# BidirectionalBusCape.net
KiCad netlist of a schematic drawn in EAGLE
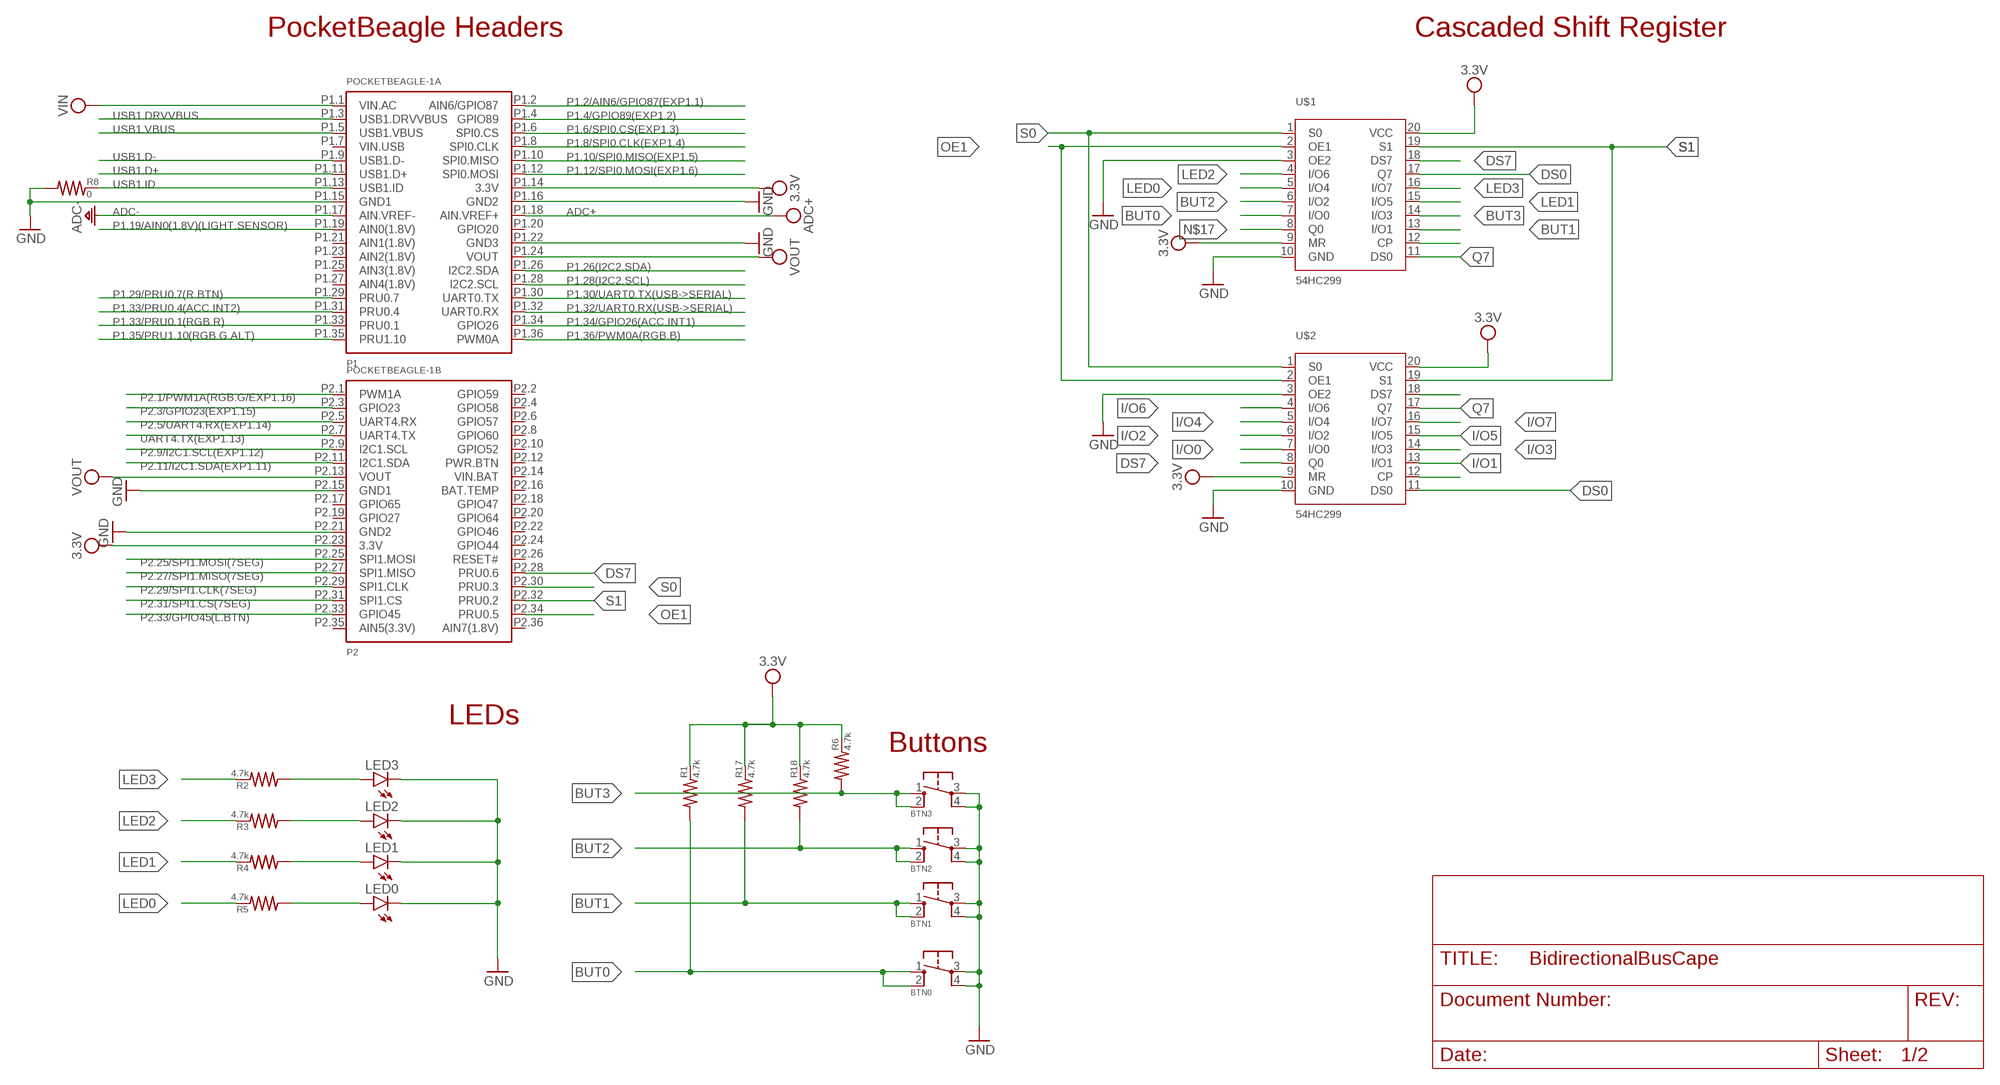
[diagram p0: schematic, sheet 1]

(export (version "E")
  (design (tool "Eeschema 10.0.6"))
  (components
    (comp (ref "BTN0")
      (value "TACTILE.SWITCH-6MM")
      (footprint "eagle-import:6MM_TACTILE-SWITCH")
      (libsource (lib "eagle-import") (part "TACTILE.SWITCH-6MM"))
    )
    (comp (ref "BTN1")
      (value "TACTILE.SWITCH-6MM")
      (footprint "eagle-import:6MM_TACTILE-SWITCH")
      (libsource (lib "eagle-import") (part "TACTILE.SWITCH-6MM"))
    )
    (comp (ref "BTN2")
      (value "TACTILE.SWITCH-6MM")
      (footprint "eagle-import:6MM_TACTILE-SWITCH")
      (libsource (lib "eagle-import") (part "TACTILE.SWITCH-6MM"))
    )
    (comp (ref "BTN3")
      (value "TACTILE.SWITCH-3X3.5MM")
      (footprint "eagle-import:3X3.5MM-TACTILE-SWITCH")
      (libsource (lib "eagle-import") (part "TACTILE.SWITCH-3X3.5MM"))
    )
    (comp (ref "LED0")
      (value "LEDCHIPLED_0603")
      (footprint "eagle-import:CHIPLED_0603")
      (libsource (lib "eagle-import") (part "LEDCHIPLED_0603"))
    )
    (comp (ref "LED1")
      (value "LEDCHIPLED_0603")
      (footprint "eagle-import:CHIPLED_0603")
      (libsource (lib "eagle-import") (part "LEDCHIPLED_0603"))
    )
    (comp (ref "LED2")
      (value "LEDCHIPLED_0603")
      (footprint "eagle-import:CHIPLED_0603")
      (libsource (lib "eagle-import") (part "LEDCHIPLED_0603"))
    )
    (comp (ref "LED3")
      (value "LEDCHIPLED_0603")
      (footprint "eagle-import:CHIPLED_0603")
      (libsource (lib "eagle-import") (part "LEDCHIPLED_0603"))
    )
    (comp (ref "POCKETBEAGLE-1")
      (value "POCKETBEAGLE-(ORIGIN-CENTER)-SMT.PADS(ONLY)-NO.RESTRICT")
      (footprint "eagle-import:POCKETBEAGLE-(ORIGIN-CENTER)-SMT.PADS(ONLY)-NO.RESTRICT")
      (libsource (lib "eagle-import") (part "POCKETBEAGLE-(ORIGIN-CENTER)-SMT.PADS(ONLY)-NO.RESTRICT"))
    )
    (comp (ref "R1")
      (value "4.7k")
      (footprint "eagle-import:0402")
      (libsource (lib "eagle-import") (part "RESISTOR-(INCH)-0402"))
    )
    (comp (ref "R2")
      (value "4.7k")
      (footprint "eagle-import:0402")
      (libsource (lib "eagle-import") (part "RESISTOR-(INCH)-0402"))
    )
    (comp (ref "R3")
      (value "4.7k")
      (footprint "eagle-import:0402")
      (libsource (lib "eagle-import") (part "RESISTOR-(INCH)-0402"))
    )
    (comp (ref "R4")
      (value "4.7k")
      (footprint "eagle-import:0402")
      (libsource (lib "eagle-import") (part "RESISTOR-(INCH)-0402"))
    )
    (comp (ref "R5")
      (value "4.7k")
      (footprint "eagle-import:0402")
      (libsource (lib "eagle-import") (part "RESISTOR-(INCH)-0402"))
    )
    (comp (ref "R6")
      (value "4.7k")
      (footprint "eagle-import:0402")
      (libsource (lib "eagle-import") (part "RESISTOR-(INCH)-0402"))
    )
    (comp (ref "R8")
      (value "0")
      (footprint "eagle-import:0402")
      (libsource (lib "eagle-import") (part "RESISTOR-(INCH)-0402"))
    )
    (comp (ref "R17")
      (value "4.7k")
      (footprint "eagle-import:0402")
      (libsource (lib "eagle-import") (part "RESISTOR-(INCH)-0402"))
    )
    (comp (ref "R18")
      (value "4.7k")
      (footprint "eagle-import:0402")
      (libsource (lib "eagle-import") (part "RESISTOR-(INCH)-0402"))
    )
    (comp (ref "U$1")
      (value "54HC299")
      (footprint "eagle-import:DIP254P762X508-20P")
      (libsource (lib "eagle-import") (part "54HC299"))
    )
    (comp (ref "U$2")
      (value "54HC299")
      (footprint "eagle-import:DIP254P762X508-20P")
      (libsource (lib "eagle-import") (part "54HC299"))
    )
  )
  (nets
    (net (code "1") (name "3.3V") (class "Default")
      (node (ref "POCKETBEAGLE-1") (pin "P1.14") (pinfunction "3.3V_P1.14") (pintype "bidirectional"))
      (node (ref "POCKETBEAGLE-1") (pin "P2.23") (pinfunction "3.3V_P2.23") (pintype "bidirectional"))
      (node (ref "R1") (pin "2") (pinfunction "2_2") (pintype "bidirectional"))
      (node (ref "R17") (pin "2") (pinfunction "2_2") (pintype "bidirectional"))
      (node (ref "R18") (pin "2") (pinfunction "2_2") (pintype "bidirectional"))
      (node (ref "R6") (pin "2") (pinfunction "2_2") (pintype "bidirectional"))
      (node (ref "U$1") (pin "20") (pinfunction "VCC_20") (pintype "bidirectional"))
      (node (ref "U$1") (pin "9") (pinfunction "MR_9") (pintype "bidirectional"))
      (node (ref "U$2") (pin "20") (pinfunction "VCC_20") (pintype "bidirectional"))
      (node (ref "U$2") (pin "9") (pinfunction "MR_9") (pintype "bidirectional"))
    )
    (net (code "2") (name "ADC+") (class "Default")
      (node (ref "POCKETBEAGLE-1") (pin "P1.18") (pinfunction "AIN.VREF+_P1.18") (pintype "bidirectional"))
    )
    (net (code "3") (name "ADC-") (class "Default")
      (node (ref "POCKETBEAGLE-1") (pin "P1.17") (pinfunction "AIN.VREF-_P1.17") (pintype "bidirectional"))
    )
    (net (code "4") (name "BUT0") (class "Default")
      (node (ref "BTN0") (pin "1") (pinfunction "1_1") (pintype "bidirectional"))
      (node (ref "BTN0") (pin "2") (pinfunction "2_2") (pintype "bidirectional"))
      (node (ref "R1") (pin "1") (pinfunction "1_1") (pintype "bidirectional"))
      (node (ref "U$1") (pin "7") (pinfunction "I/O0_7") (pintype "bidirectional"))
    )
    (net (code "5") (name "BUT1") (class "Default")
      (node (ref "BTN1") (pin "1") (pinfunction "1_1") (pintype "bidirectional"))
      (node (ref "BTN1") (pin "2") (pinfunction "2_2") (pintype "bidirectional"))
      (node (ref "R17") (pin "1") (pinfunction "1_1") (pintype "bidirectional"))
      (node (ref "U$1") (pin "13") (pinfunction "I/O1_13") (pintype "bidirectional"))
    )
    (net (code "6") (name "BUT2") (class "Default")
      (node (ref "BTN2") (pin "1") (pinfunction "1_1") (pintype "bidirectional"))
      (node (ref "BTN2") (pin "2") (pinfunction "2_2") (pintype "bidirectional"))
      (node (ref "R18") (pin "1") (pinfunction "1_1") (pintype "bidirectional"))
      (node (ref "U$1") (pin "6") (pinfunction "I/O2_6") (pintype "bidirectional"))
    )
    (net (code "7") (name "BUT3") (class "Default")
      (node (ref "BTN3") (pin "1") (pinfunction "1_1") (pintype "bidirectional"))
      (node (ref "BTN3") (pin "2") (pinfunction "2_2") (pintype "bidirectional"))
      (node (ref "R6") (pin "1") (pinfunction "1_1") (pintype "bidirectional"))
      (node (ref "U$1") (pin "14") (pinfunction "I/O3_14") (pintype "bidirectional"))
    )
    (net (code "8") (name "DS0") (class "Default")
      (node (ref "U$1") (pin "17") (pinfunction "Q7_17") (pintype "bidirectional"))
      (node (ref "U$2") (pin "11") (pinfunction "DS0_11") (pintype "bidirectional"))
    )
    (net (code "9") (name "DS7") (class "Default")
      (node (ref "POCKETBEAGLE-1") (pin "P2.28") (pinfunction "PRU0.6_P2.28") (pintype "bidirectional"))
      (node (ref "U$1") (pin "18") (pinfunction "DS7_18") (pintype "bidirectional"))
      (node (ref "U$2") (pin "8") (pinfunction "Q0_8") (pintype "bidirectional"))
    )
    (net (code "10") (name "GND") (class "Default")
      (node (ref "BTN0") (pin "3") (pinfunction "3_3") (pintype "bidirectional"))
      (node (ref "BTN0") (pin "4") (pinfunction "4_4") (pintype "bidirectional"))
      (node (ref "BTN1") (pin "3") (pinfunction "3_3") (pintype "bidirectional"))
      (node (ref "BTN1") (pin "4") (pinfunction "4_4") (pintype "bidirectional"))
      (node (ref "BTN2") (pin "3") (pinfunction "3_3") (pintype "bidirectional"))
      (node (ref "BTN2") (pin "4") (pinfunction "4_4") (pintype "bidirectional"))
      (node (ref "BTN3") (pin "3") (pinfunction "3_3") (pintype "bidirectional"))
      (node (ref "BTN3") (pin "4") (pinfunction "4_4") (pintype "bidirectional"))
      (node (ref "LED0") (pin "C") (pinfunction "C_C") (pintype "passive"))
      (node (ref "LED1") (pin "C") (pinfunction "C_C") (pintype "passive"))
      (node (ref "LED2") (pin "C") (pinfunction "C_C") (pintype "passive"))
      (node (ref "LED3") (pin "C") (pinfunction "C_C") (pintype "passive"))
      (node (ref "POCKETBEAGLE-1") (pin "P1.15") (pinfunction "GND1_P1.15") (pintype "bidirectional"))
      (node (ref "POCKETBEAGLE-1") (pin "P1.16") (pinfunction "GND2_P1.16") (pintype "bidirectional"))
      (node (ref "POCKETBEAGLE-1") (pin "P1.22") (pinfunction "GND3_P1.22") (pintype "bidirectional"))
      (node (ref "POCKETBEAGLE-1") (pin "P2.15") (pinfunction "GND1_P2.15") (pintype "bidirectional"))
      (node (ref "POCKETBEAGLE-1") (pin "P2.21") (pinfunction "GND2_P2.21") (pintype "bidirectional"))
      (node (ref "R8") (pin "1") (pinfunction "1_1") (pintype "bidirectional"))
      (node (ref "U$1") (pin "10") (pinfunction "GND_10") (pintype "bidirectional"))
      (node (ref "U$1") (pin "3") (pinfunction "OE2_3") (pintype "bidirectional"))
      (node (ref "U$2") (pin "10") (pinfunction "GND_10") (pintype "bidirectional"))
      (node (ref "U$2") (pin "3") (pinfunction "OE2_3") (pintype "bidirectional"))
    )
    (net (code "11") (name "I{slash}O0") (class "Default")
      (node (ref "U$2") (pin "7") (pinfunction "I/O0_7") (pintype "bidirectional"))
    )
    (net (code "12") (name "I{slash}O1") (class "Default")
      (node (ref "U$2") (pin "13") (pinfunction "I/O1_13") (pintype "bidirectional"))
    )
    (net (code "13") (name "I{slash}O2") (class "Default")
      (node (ref "U$2") (pin "6") (pinfunction "I/O2_6") (pintype "bidirectional"))
    )
    (net (code "14") (name "I{slash}O3") (class "Default")
      (node (ref "U$2") (pin "14") (pinfunction "I/O3_14") (pintype "bidirectional"))
    )
    (net (code "15") (name "I{slash}O4") (class "Default")
      (node (ref "U$2") (pin "5") (pinfunction "I/O4_5") (pintype "bidirectional"))
    )
    (net (code "16") (name "I{slash}O5") (class "Default")
      (node (ref "U$2") (pin "15") (pinfunction "I/O5_15") (pintype "bidirectional"))
    )
    (net (code "17") (name "I{slash}O6") (class "Default")
      (node (ref "U$2") (pin "4") (pinfunction "I/O6_4") (pintype "bidirectional"))
    )
    (net (code "18") (name "I{slash}O7") (class "Default")
      (node (ref "U$2") (pin "16") (pinfunction "I/O7_16") (pintype "bidirectional"))
    )
    (net (code "19") (name "LED0") (class "Default")
      (node (ref "R5") (pin "2") (pinfunction "2_2") (pintype "bidirectional"))
      (node (ref "U$1") (pin "5") (pinfunction "I/O4_5") (pintype "bidirectional"))
    )
    (net (code "20") (name "LED1") (class "Default")
      (node (ref "R4") (pin "2") (pinfunction "2_2") (pintype "bidirectional"))
      (node (ref "U$1") (pin "15") (pinfunction "I/O5_15") (pintype "bidirectional"))
    )
    (net (code "21") (name "LED2") (class "Default")
      (node (ref "R3") (pin "2") (pinfunction "2_2") (pintype "bidirectional"))
      (node (ref "U$1") (pin "4") (pinfunction "I/O6_4") (pintype "bidirectional"))
    )
    (net (code "22") (name "LED3") (class "Default")
      (node (ref "R2") (pin "2") (pinfunction "2_2") (pintype "bidirectional"))
      (node (ref "U$1") (pin "16") (pinfunction "I/O7_16") (pintype "bidirectional"))
    )
    (net (code "23") (name "N$17") (class "Default")
      (node (ref "U$1") (pin "8") (pinfunction "Q0_8") (pintype "bidirectional"))
    )
    (net (code "24") (name "Net-(LED0-PadA)") (class "Default")
      (node (ref "LED0") (pin "A") (pinfunction "A_A") (pintype "passive"))
      (node (ref "R5") (pin "1") (pinfunction "1_1") (pintype "bidirectional"))
    )
    (net (code "25") (name "Net-(LED1-PadA)") (class "Default")
      (node (ref "LED1") (pin "A") (pinfunction "A_A") (pintype "passive"))
      (node (ref "R4") (pin "1") (pinfunction "1_1") (pintype "bidirectional"))
    )
    (net (code "26") (name "Net-(LED2-PadA)") (class "Default")
      (node (ref "LED2") (pin "A") (pinfunction "A_A") (pintype "passive"))
      (node (ref "R3") (pin "1") (pinfunction "1_1") (pintype "bidirectional"))
    )
    (net (code "27") (name "Net-(LED3-PadA)") (class "Default")
      (node (ref "LED3") (pin "A") (pinfunction "A_A") (pintype "passive"))
      (node (ref "R2") (pin "1") (pinfunction "1_1") (pintype "bidirectional"))
    )
    (net (code "28") (name "OE1") (class "Default")
      (node (ref "POCKETBEAGLE-1") (pin "P2.34") (pinfunction "PRU0.5_P2.34") (pintype "bidirectional"))
      (node (ref "U$1") (pin "2") (pinfunction "OE1_2") (pintype "bidirectional"))
      (node (ref "U$2") (pin "2") (pinfunction "OE1_2") (pintype "bidirectional"))
    )
    (net (code "29") (name "P1.2{slash}AIN6{slash}GPIO87(EXP1.1)") (class "Default")
      (node (ref "POCKETBEAGLE-1") (pin "P1.2") (pinfunction "AIN6/GPIO87_P1.2") (pintype "bidirectional"))
    )
    (net (code "30") (name "P1.4{slash}GPIO89(EXP1.2)") (class "Default")
      (node (ref "POCKETBEAGLE-1") (pin "P1.4") (pinfunction "GPIO89_P1.4") (pintype "bidirectional"))
    )
    (net (code "31") (name "P1.6{slash}SPI0.CS(EXP1.3)") (class "Default")
      (node (ref "POCKETBEAGLE-1") (pin "P1.6") (pinfunction "SPI0.CS_P1.6") (pintype "bidirectional"))
    )
    (net (code "32") (name "P1.8{slash}SPI0.CLK(EXP1.4)") (class "Default")
      (node (ref "POCKETBEAGLE-1") (pin "P1.8") (pinfunction "SPI0.CLK_P1.8") (pintype "bidirectional"))
    )
    (net (code "33") (name "P1.10{slash}SPI0.MISO(EXP1.5)") (class "Default")
      (node (ref "POCKETBEAGLE-1") (pin "P1.10") (pinfunction "SPI0.MISO_P1.10") (pintype "bidirectional"))
    )
    (net (code "34") (name "P1.12{slash}SPI0.MOSI(EXP1.6)") (class "Default")
      (node (ref "POCKETBEAGLE-1") (pin "P1.12") (pinfunction "SPI0.MOSI_P1.12") (pintype "bidirectional"))
    )
    (net (code "35") (name "P1.19{slash}AIN0(1.8V)(LIGHT.SENSOR)") (class "Default")
      (node (ref "POCKETBEAGLE-1") (pin "P1.19") (pinfunction "AIN0(1.8V)_P1.19") (pintype "bidirectional"))
    )
    (net (code "36") (name "P1.26(I2C2.SDA)") (class "Default")
      (node (ref "POCKETBEAGLE-1") (pin "P1.26") (pinfunction "I2C2.SDA_P1.26") (pintype "bidirectional"))
    )
    (net (code "37") (name "P1.28(I2C2.SCL)") (class "Default")
      (node (ref "POCKETBEAGLE-1") (pin "P1.28") (pinfunction "I2C2.SCL_P1.28") (pintype "bidirectional"))
    )
    (net (code "38") (name "P1.29{slash}PRU0.7(R.BTN)") (class "Default")
      (node (ref "POCKETBEAGLE-1") (pin "P1.29") (pinfunction "PRU0.7_P1.29") (pintype "bidirectional"))
    )
    (net (code "39") (name "P1.30{slash}UART0.TX(USB->SERIAL)") (class "Default")
      (node (ref "POCKETBEAGLE-1") (pin "P1.30") (pinfunction "UART0.TX_P1.30") (pintype "bidirectional"))
    )
    (net (code "40") (name "P1.32{slash}UART0.RX(USB->SERIAL)") (class "Default")
      (node (ref "POCKETBEAGLE-1") (pin "P1.32") (pinfunction "UART0.RX_P1.32") (pintype "bidirectional"))
    )
    (net (code "41") (name "P1.33{slash}PRU0.1(RGB.R)") (class "Default")
      (node (ref "POCKETBEAGLE-1") (pin "P1.33") (pinfunction "PRU0.1_P1.33") (pintype "bidirectional"))
    )
    (net (code "42") (name "P1.33{slash}PRU0.4(ACC.INT2)") (class "Default")
      (node (ref "POCKETBEAGLE-1") (pin "P1.31") (pinfunction "PRU0.4_P1.31") (pintype "bidirectional"))
    )
    (net (code "43") (name "P1.34{slash}GPIO26(ACC.INT1)") (class "Default")
      (node (ref "POCKETBEAGLE-1") (pin "P1.34") (pinfunction "GPIO26_P1.34") (pintype "bidirectional"))
    )
    (net (code "44") (name "P1.35{slash}PRU1.10(RGB.G.ALT)") (class "Default")
      (node (ref "POCKETBEAGLE-1") (pin "P1.35") (pinfunction "PRU1.10_P1.35") (pintype "bidirectional"))
    )
    (net (code "45") (name "P1.36{slash}PWM0A(RGB.B)") (class "Default")
      (node (ref "POCKETBEAGLE-1") (pin "P1.36") (pinfunction "PWM0A_P1.36") (pintype "bidirectional"))
    )
    (net (code "46") (name "P2.1{slash}PWM1A(RGB.G{slash}EXP1.16)") (class "Default")
      (node (ref "POCKETBEAGLE-1") (pin "P2.1") (pinfunction "PWM1A_P2.1") (pintype "bidirectional"))
    )
    (net (code "47") (name "P2.3{slash}GPIO23(EXP1.15)") (class "Default")
      (node (ref "POCKETBEAGLE-1") (pin "P2.3") (pinfunction "GPIO23_P2.3") (pintype "bidirectional"))
    )
    (net (code "48") (name "P2.5{slash}UART4.RX(EXP1.14)") (class "Default")
      (node (ref "POCKETBEAGLE-1") (pin "P2.5") (pinfunction "UART4.RX_P2.5") (pintype "bidirectional"))
    )
    (net (code "49") (name "P2.9{slash}I2C1.SCL(EXP1.12)") (class "Default")
      (node (ref "POCKETBEAGLE-1") (pin "P2.9") (pinfunction "I2C1.SCL_P2.9") (pintype "bidirectional"))
    )
    (net (code "50") (name "P2.11{slash}I2C1.SDA(EXP1.11)") (class "Default")
      (node (ref "POCKETBEAGLE-1") (pin "P2.11") (pinfunction "I2C1.SDA_P2.11") (pintype "bidirectional"))
    )
    (net (code "51") (name "P2.25{slash}SPI1.MOSI(7SEG)") (class "Default")
      (node (ref "POCKETBEAGLE-1") (pin "P2.25") (pinfunction "SPI1.MOSI_P2.25") (pintype "bidirectional"))
    )
    (net (code "52") (name "P2.27{slash}SPI1.MISO(7SEG)") (class "Default")
      (node (ref "POCKETBEAGLE-1") (pin "P2.27") (pinfunction "SPI1.MISO_P2.27") (pintype "bidirectional"))
    )
    (net (code "53") (name "P2.29{slash}SPI1.CLK(7SEG)") (class "Default")
      (node (ref "POCKETBEAGLE-1") (pin "P2.29") (pinfunction "SPI1.CLK_P2.29") (pintype "bidirectional"))
    )
    (net (code "54") (name "P2.31{slash}SPI1.CS(7SEG)") (class "Default")
      (node (ref "POCKETBEAGLE-1") (pin "P2.31") (pinfunction "SPI1.CS_P2.31") (pintype "bidirectional"))
    )
    (net (code "55") (name "P2.33{slash}GPIO45(L.BTN)") (class "Default")
      (node (ref "POCKETBEAGLE-1") (pin "P2.33") (pinfunction "GPIO45_P2.33") (pintype "bidirectional"))
    )
    (net (code "56") (name "Q7") (class "Default")
      (node (ref "U$1") (pin "11") (pinfunction "DS0_11") (pintype "bidirectional"))
      (node (ref "U$2") (pin "17") (pinfunction "Q7_17") (pintype "bidirectional"))
    )
    (net (code "57") (name "S0") (class "Default")
      (node (ref "POCKETBEAGLE-1") (pin "P2.30") (pinfunction "PRU0.3_P2.30") (pintype "bidirectional"))
      (node (ref "U$1") (pin "1") (pinfunction "S0_1") (pintype "bidirectional"))
      (node (ref "U$2") (pin "1") (pinfunction "S0_1") (pintype "bidirectional"))
    )
    (net (code "58") (name "S1") (class "Default")
      (node (ref "POCKETBEAGLE-1") (pin "P2.32") (pinfunction "PRU0.2_P2.32") (pintype "bidirectional"))
      (node (ref "U$1") (pin "19") (pinfunction "S1_19") (pintype "bidirectional"))
      (node (ref "U$2") (pin "19") (pinfunction "S1_19") (pintype "bidirectional"))
    )
    (net (code "59") (name "UART4.TX(EXP1.13)") (class "Default")
      (node (ref "POCKETBEAGLE-1") (pin "P2.7") (pinfunction "UART4.TX_P2.7") (pintype "bidirectional"))
    )
    (net (code "60") (name "USB1.D+") (class "Default")
      (node (ref "POCKETBEAGLE-1") (pin "P1.11") (pinfunction "USB1.D+_P1.11") (pintype "bidirectional"))
    )
    (net (code "61") (name "USB1.D-") (class "Default")
      (node (ref "POCKETBEAGLE-1") (pin "P1.9") (pinfunction "USB1.D-_P1.9") (pintype "bidirectional"))
    )
    (net (code "62") (name "USB1.DRVVBUS") (class "Default")
      (node (ref "POCKETBEAGLE-1") (pin "P1.3") (pinfunction "USB1.DRVVBUS_P1.3") (pintype "bidirectional"))
    )
    (net (code "63") (name "USB1.ID") (class "Default")
      (node (ref "POCKETBEAGLE-1") (pin "P1.13") (pinfunction "USB1.ID_P1.13") (pintype "bidirectional"))
      (node (ref "R8") (pin "2") (pinfunction "2_2") (pintype "bidirectional"))
    )
    (net (code "64") (name "USB1.VBUS") (class "Default")
      (node (ref "POCKETBEAGLE-1") (pin "P1.5") (pinfunction "USB1.VBUS_P1.5") (pintype "bidirectional"))
    )
    (net (code "65") (name "VIN") (class "Default")
      (node (ref "POCKETBEAGLE-1") (pin "P1.1") (pinfunction "VIN.AC_P1.1") (pintype "bidirectional"))
    )
    (net (code "66") (name "VOUT") (class "Default")
      (node (ref "POCKETBEAGLE-1") (pin "P1.24") (pinfunction "VOUT_P1.24") (pintype "bidirectional"))
      (node (ref "POCKETBEAGLE-1") (pin "P2.13") (pinfunction "VOUT_P2.13") (pintype "bidirectional"))
    )
    (net (code "67") (name "unconnected-(POCKETBEAGLE-1A-AIN1(1.8V)-PadP1.21)") (class "Default")
      (node (ref "POCKETBEAGLE-1") (pin "P1.21") (pinfunction "AIN1(1.8V)_P1.21") (pintype "bidirectional"))
    )
    (net (code "68") (name "unconnected-(POCKETBEAGLE-1A-AIN2(1.8V)-PadP1.23)") (class "Default")
      (node (ref "POCKETBEAGLE-1") (pin "P1.23") (pinfunction "AIN2(1.8V)_P1.23") (pintype "bidirectional"))
    )
    (net (code "69") (name "unconnected-(POCKETBEAGLE-1A-AIN3(1.8V)-PadP1.25)") (class "Default")
      (node (ref "POCKETBEAGLE-1") (pin "P1.25") (pinfunction "AIN3(1.8V)_P1.25") (pintype "bidirectional"))
    )
    (net (code "70") (name "unconnected-(POCKETBEAGLE-1A-AIN4(1.8V)-PadP1.27)") (class "Default")
      (node (ref "POCKETBEAGLE-1") (pin "P1.27") (pinfunction "AIN4(1.8V)_P1.27") (pintype "bidirectional"))
    )
    (net (code "71") (name "unconnected-(POCKETBEAGLE-1A-GPIO20-PadP1.20)") (class "Default")
      (node (ref "POCKETBEAGLE-1") (pin "P1.20") (pinfunction "GPIO20_P1.20") (pintype "bidirectional"))
    )
    (net (code "72") (name "unconnected-(POCKETBEAGLE-1A-VIN.USB-PadP1.7)") (class "Default")
      (node (ref "POCKETBEAGLE-1") (pin "P1.7") (pinfunction "VIN.USB_P1.7") (pintype "bidirectional"))
    )
    (net (code "73") (name "unconnected-(POCKETBEAGLE-1B-AIN5(3.3V)-PadP2.35)") (class "Default")
      (node (ref "POCKETBEAGLE-1") (pin "P2.35") (pinfunction "AIN5(3.3V)_P2.35") (pintype "bidirectional"))
    )
    (net (code "74") (name "unconnected-(POCKETBEAGLE-1B-AIN7(1.8V)-PadP2.36)") (class "Default")
      (node (ref "POCKETBEAGLE-1") (pin "P2.36") (pinfunction "AIN7(1.8V)_P2.36") (pintype "bidirectional"))
    )
    (net (code "75") (name "unconnected-(POCKETBEAGLE-1B-BAT.TEMP-PadP2.16)") (class "Default")
      (node (ref "POCKETBEAGLE-1") (pin "P2.16") (pinfunction "BAT.TEMP_P2.16") (pintype "bidirectional"))
    )
    (net (code "76") (name "unconnected-(POCKETBEAGLE-1B-GPIO27-PadP2.19)") (class "Default")
      (node (ref "POCKETBEAGLE-1") (pin "P2.19") (pinfunction "GPIO27_P2.19") (pintype "bidirectional"))
    )
    (net (code "77") (name "unconnected-(POCKETBEAGLE-1B-GPIO44-PadP2.24)") (class "Default")
      (node (ref "POCKETBEAGLE-1") (pin "P2.24") (pinfunction "GPIO44_P2.24") (pintype "bidirectional"))
    )
    (net (code "78") (name "unconnected-(POCKETBEAGLE-1B-GPIO46-PadP2.22)") (class "Default")
      (node (ref "POCKETBEAGLE-1") (pin "P2.22") (pinfunction "GPIO46_P2.22") (pintype "bidirectional"))
    )
    (net (code "79") (name "unconnected-(POCKETBEAGLE-1B-GPIO47-PadP2.18)") (class "Default")
      (node (ref "POCKETBEAGLE-1") (pin "P2.18") (pinfunction "GPIO47_P2.18") (pintype "bidirectional"))
    )
    (net (code "80") (name "unconnected-(POCKETBEAGLE-1B-GPIO52-PadP2.10)") (class "Default")
      (node (ref "POCKETBEAGLE-1") (pin "P2.10") (pinfunction "GPIO52_P2.10") (pintype "bidirectional"))
    )
    (net (code "81") (name "unconnected-(POCKETBEAGLE-1B-GPIO57-PadP2.6)") (class "Default")
      (node (ref "POCKETBEAGLE-1") (pin "P2.6") (pinfunction "GPIO57_P2.6") (pintype "bidirectional"))
    )
    (net (code "82") (name "unconnected-(POCKETBEAGLE-1B-GPIO58-PadP2.4)") (class "Default")
      (node (ref "POCKETBEAGLE-1") (pin "P2.4") (pinfunction "GPIO58_P2.4") (pintype "bidirectional"))
    )
    (net (code "83") (name "unconnected-(POCKETBEAGLE-1B-GPIO59-PadP2.2)") (class "Default")
      (node (ref "POCKETBEAGLE-1") (pin "P2.2") (pinfunction "GPIO59_P2.2") (pintype "bidirectional"))
    )
    (net (code "84") (name "unconnected-(POCKETBEAGLE-1B-GPIO60-PadP2.8)") (class "Default")
      (node (ref "POCKETBEAGLE-1") (pin "P2.8") (pinfunction "GPIO60_P2.8") (pintype "bidirectional"))
    )
    (net (code "85") (name "unconnected-(POCKETBEAGLE-1B-GPIO64-PadP2.20)") (class "Default")
      (node (ref "POCKETBEAGLE-1") (pin "P2.20") (pinfunction "GPIO64_P2.20") (pintype "bidirectional"))
    )
    (net (code "86") (name "unconnected-(POCKETBEAGLE-1B-GPIO65-PadP2.17)") (class "Default")
      (node (ref "POCKETBEAGLE-1") (pin "P2.17") (pinfunction "GPIO65_P2.17") (pintype "bidirectional"))
    )
    (net (code "87") (name "unconnected-(POCKETBEAGLE-1B-PWR.BTN-PadP2.12)") (class "Default")
      (node (ref "POCKETBEAGLE-1") (pin "P2.12") (pinfunction "PWR.BTN_P2.12") (pintype "bidirectional"))
    )
    (net (code "88") (name "unconnected-(POCKETBEAGLE-1B-RESET#-PadP2.26)") (class "Default")
      (node (ref "POCKETBEAGLE-1") (pin "P2.26") (pinfunction "RESET#_P2.26") (pintype "bidirectional"))
    )
    (net (code "89") (name "unconnected-(POCKETBEAGLE-1B-VIN.BAT-PadP2.14)") (class "Default")
      (node (ref "POCKETBEAGLE-1") (pin "P2.14") (pinfunction "VIN.BAT_P2.14") (pintype "bidirectional"))
    )
    (net (code "90") (name "unconnected-(U$1-CP-Pad12)") (class "Default")
      (node (ref "U$1") (pin "12") (pinfunction "CP_12") (pintype "bidirectional"))
    )
    (net (code "91") (name "unconnected-(U$2-CP-Pad12)") (class "Default")
      (node (ref "U$2") (pin "12") (pinfunction "CP_12") (pintype "bidirectional"))
    )
    (net (code "92") (name "unconnected-(U$2-DS7-Pad18)") (class "Default")
      (node (ref "U$2") (pin "18") (pinfunction "DS7_18") (pintype "bidirectional"))
    )
  )
)
